# 15_LMS2_RF1_Misc.net
KiCad netlist of a schematic drawn in Altium Designer
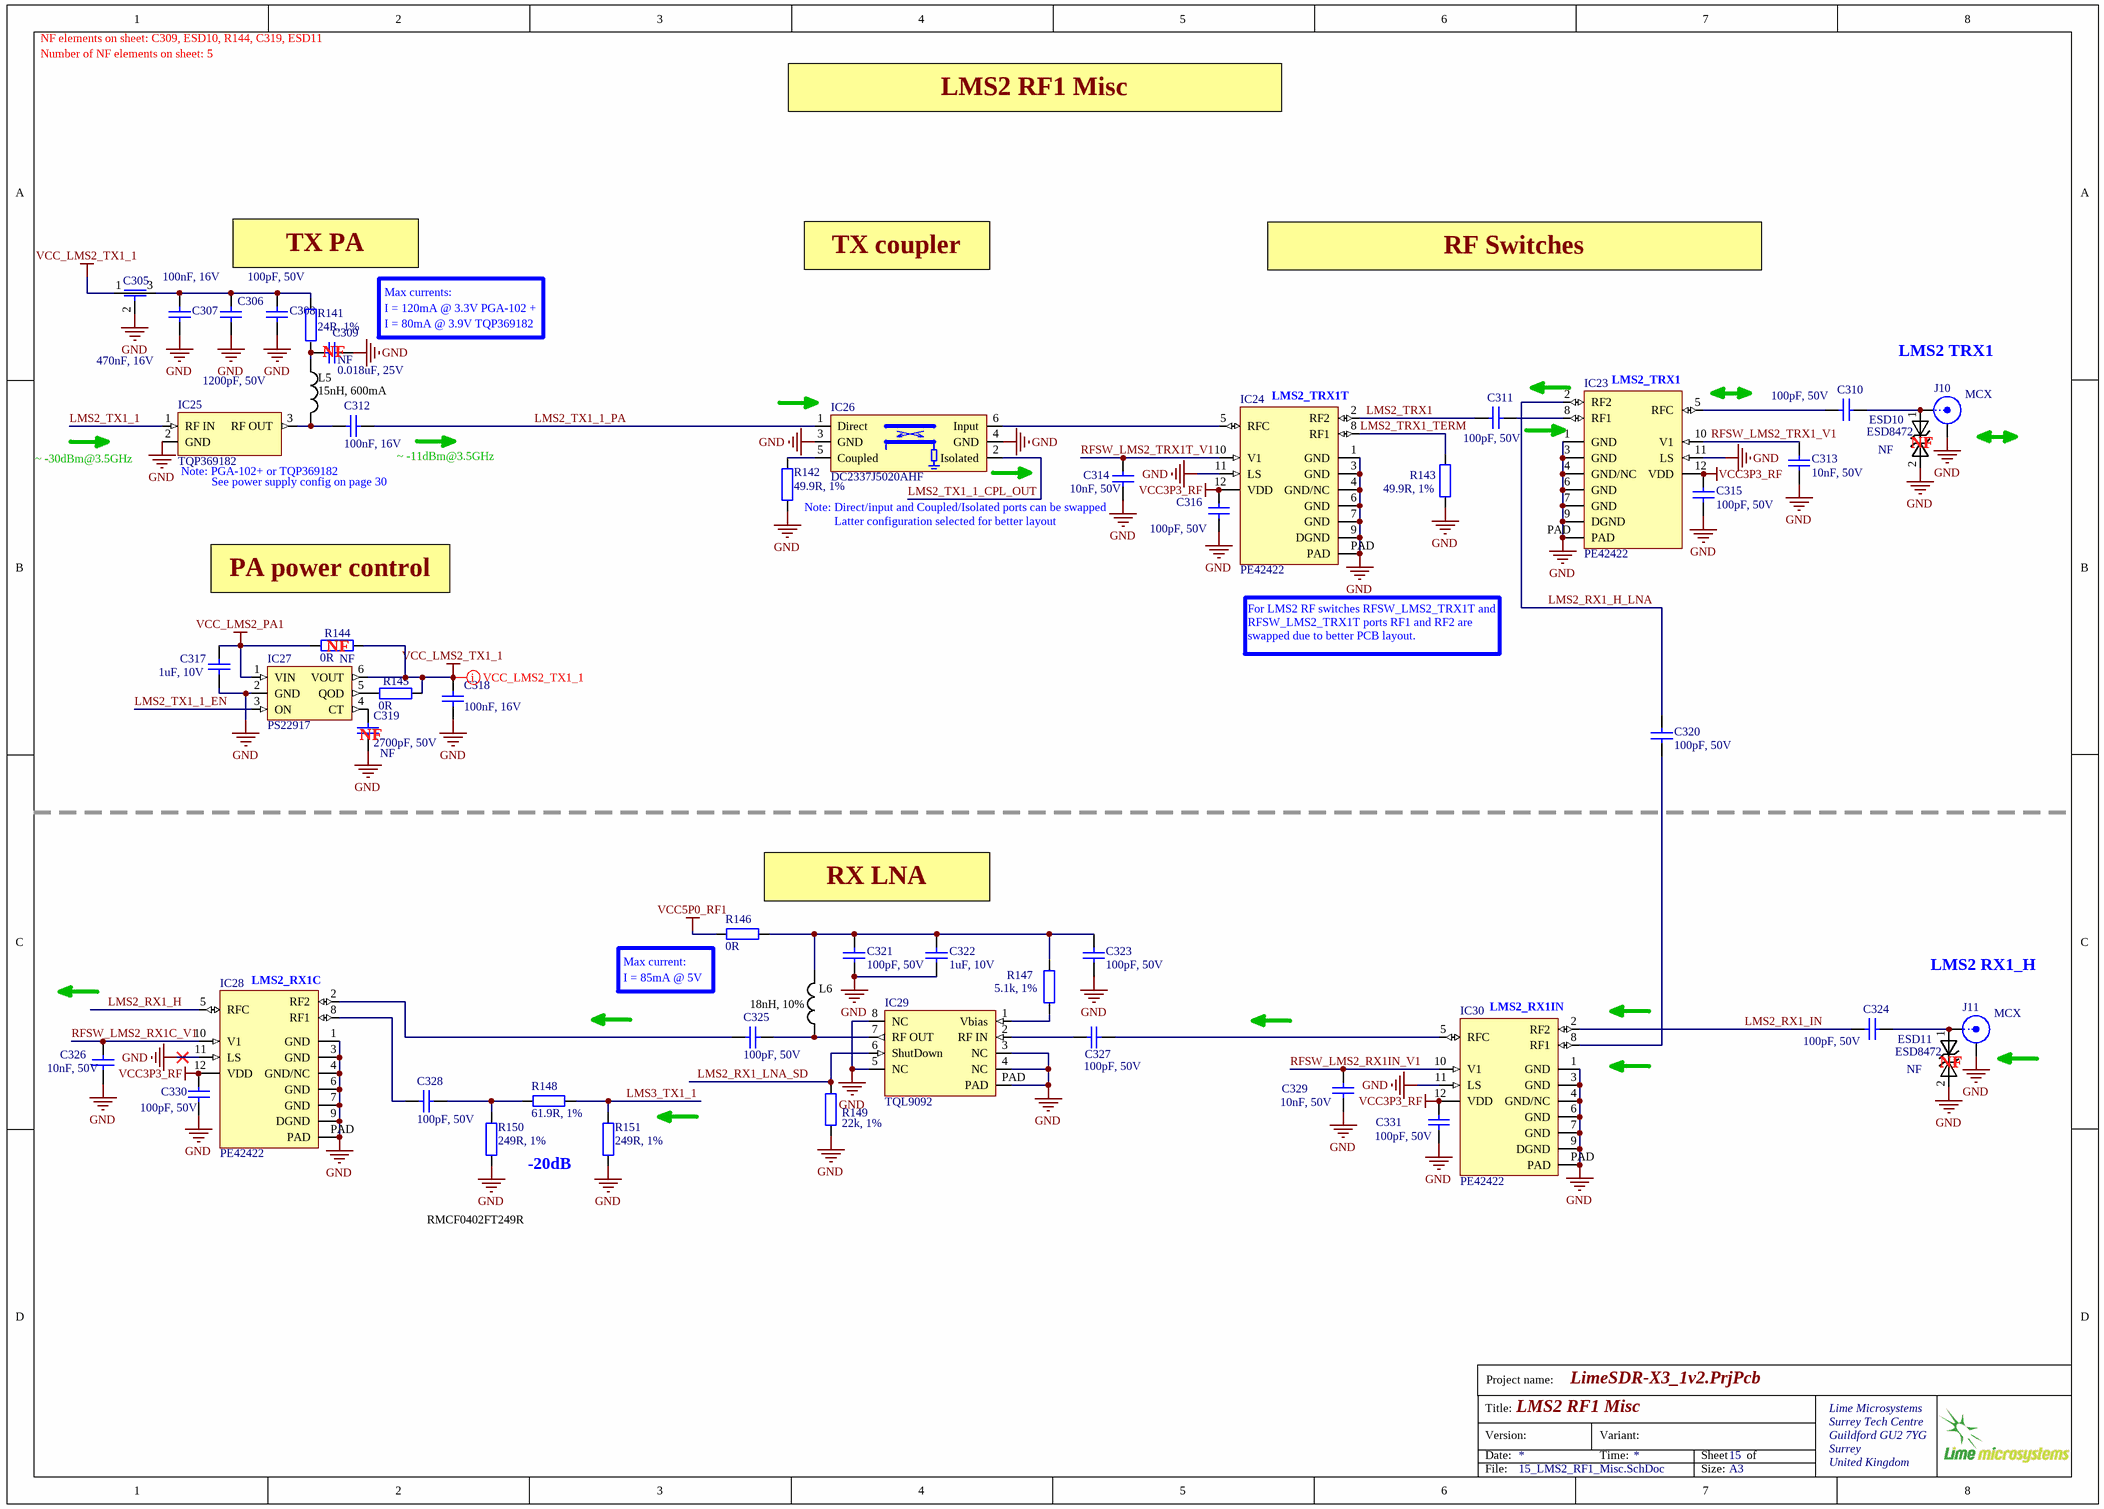
[diagram p0: 15_LMS2_RF1_Misc.SchDoc]

(export (version "E")
  (design (tool "Eeschema 10.0.6"))
  (components
    (comp (ref "C305")
      (value "470nF, 16V")
      (footprint "CAP0805_FEEDTHROUGH")
      (fields
        (field (name "MANUFACTURER") "Murata")
        (field (name "TOLERANCE") "20%")
        (field (name "VOLTAGE") "16V")
      )
      (libsource (lib "LimeMicroAltiumLib_schLib_r01") (part "Cap_feed_through"))
    )
    (comp (ref "C306")
      (value "1200pF, 50V")
      (footprint "CAP0402")
      (fields (field (name "MANUFACTURER") "Kemet") (field (name "TOLERANCE") "±5%"))
      (libsource (lib "") (part "Cap_0402_11"))
    )
    (comp (ref "C307")
      (value "100nF, 16V")
      (footprint "CAP0402")
      (fields (field (name "MANUFACTURER") "Murata Electronics") (field (name "TOLERANCE") "10 %"))
      (libsource (lib "") (part "Cap_0402_2"))
    )
    (comp (ref "C308")
      (value "100pF, 50V")
      (footprint "CAP0402")
      (fields (field (name "TOLERANCE") "±5%") (field (name "MANUFACTURER") "Yageo"))
      (libsource (lib "") (part "Cap_0402_2"))
    )
    (comp (ref "C309")
      (value "0.018uF, 25V")
      (footprint "CAP0402")
      (fields
        (field (name "ASSEMBLY INFO") "NF")
        (field (name "MANUFACTURER") "Yageo")
        (field (name "TOLERANCE") "10%")
      )
      (libsource (lib "") (part "Cap_0402_10"))
    )
    (comp (ref "C310")
      (value "100pF, 50V")
      (footprint "CAP0402")
      (fields (field (name "TOLERANCE") "±5%") (field (name "MANUFACTURER") "Yageo"))
      (libsource (lib "") (part "Cap_0402_1"))
    )
    (comp (ref "C311")
      (value "100pF, 50V")
      (footprint "CAP0402")
      (fields (field (name "TOLERANCE") "±5%") (field (name "MANUFACTURER") "Yageo"))
      (libsource (lib "") (part "Cap_0402_1"))
    )
    (comp (ref "C312")
      (value "100nF, 16V")
      (footprint "CAP0402")
      (fields (field (name "MANUFACTURER") "Murata Electronics") (field (name "TOLERANCE") "10 %"))
      (libsource (lib "") (part "Cap_0402_3"))
    )
    (comp (ref "C313")
      (value "10nF, 50V")
      (footprint "CAP0402")
      (fields
        (field (name "MANUFACTURER") "Murata Electronics North America")
        (field (name "TOLERANCE") "±10%")
      )
      (libsource (lib "") (part "Cap_0402_6"))
    )
    (comp (ref "C314")
      (value "10nF, 50V")
      (footprint "CAP0402")
      (fields
        (field (name "MANUFACTURER") "Murata Electronics North America")
        (field (name "TOLERANCE") "±10%")
      )
      (libsource (lib "") (part "Cap_0402_6"))
    )
    (comp (ref "C315")
      (value "100pF, 50V")
      (footprint "CAP0402")
      (fields (field (name "TOLERANCE") "±5%") (field (name "MANUFACTURER") "Yageo"))
      (libsource (lib "") (part "Cap_0402_9"))
    )
    (comp (ref "C316")
      (value "100pF, 50V")
      (footprint "CAP0402")
      (fields (field (name "TOLERANCE") "±5%") (field (name "MANUFACTURER") "Yageo"))
      (libsource (lib "") (part "Cap_0402_9"))
    )
    (comp (ref "C317")
      (value "1uF, 10V")
      (footprint "CAP0402")
      (fields (field (name "MANUFACTURER") "TDK"))
      (libsource (lib "LimeMicroAltiumLib_schLib") (part "Cap_0402"))
    )
    (comp (ref "C318")
      (value "100nF, 16V")
      (footprint "CAP0402")
      (fields (field (name "MANUFACTURER") "Murata Electronics") (field (name "TOLERANCE") "10 %"))
      (libsource (lib "LimeMicroAltiumLib_schLib") (part "Cap_0402"))
    )
    (comp (ref "C319")
      (value "2700pF, 50V")
      (footprint "CAP0402")
      (fields
        (field (name "ASSEMBLY INFO") "NF")
        (field (name "TOLERANCE") "±10%")
        (field (name "MANUFACTURER") "Murata Electronics North America")
      )
      (libsource (lib "") (part "Cap_0402_2"))
    )
    (comp (ref "C320")
      (value "100pF, 50V")
      (footprint "CAP0402")
      (fields (field (name "TOLERANCE") "±5%") (field (name "MANUFACTURER") "Yageo"))
      (libsource (lib "") (part "Cap_0402_1"))
    )
    (comp (ref "C321")
      (value "100pF, 50V")
      (footprint "CAP0402")
      (fields (field (name "TOLERANCE") "±5%") (field (name "MANUFACTURER") "Yageo"))
      (libsource (lib "") (part "Cap_0402_7"))
    )
    (comp (ref "C322")
      (value "1uF, 10V")
      (footprint "CAP0402")
      (fields (field (name "MANUFACTURER") "TDK"))
      (libsource (lib "") (part "Cap_0402_4"))
    )
    (comp (ref "C323")
      (value "100pF, 50V")
      (footprint "CAP0402")
      (fields (field (name "TOLERANCE") "±5%") (field (name "MANUFACTURER") "Yageo"))
      (libsource (lib "") (part "Cap_0402_7"))
    )
    (comp (ref "C324")
      (value "100pF, 50V")
      (footprint "CAP0402")
      (fields (field (name "TOLERANCE") "±5%") (field (name "MANUFACTURER") "Yageo"))
      (libsource (lib "") (part "Cap_0402_1"))
    )
    (comp (ref "C325")
      (value "100pF, 50V")
      (footprint "CAP0402")
      (fields (field (name "TOLERANCE") "±5%") (field (name "MANUFACTURER") "Yageo"))
      (libsource (lib "LimeMicroAltiumLib_schLib") (part "Cap_0402"))
    )
    (comp (ref "C326")
      (value "10nF, 50V")
      (footprint "CAP0402")
      (fields
        (field (name "MANUFACTURER") "Murata Electronics North America")
        (field (name "TOLERANCE") "±10%")
      )
      (libsource (lib "") (part "Cap_0402_5"))
    )
    (comp (ref "C327")
      (value "100pF, 50V")
      (footprint "CAP0402")
      (fields (field (name "TOLERANCE") "±5%") (field (name "MANUFACTURER") "Yageo"))
      (libsource (lib "LimeMicroAltiumLib_schLib") (part "Cap_0402"))
    )
    (comp (ref "C328")
      (value "100pF, 50V")
      (footprint "CAP0402")
      (fields (field (name "TOLERANCE") "±5%") (field (name "MANUFACTURER") "Yageo"))
      (libsource (lib "") (part "Cap_0402_1"))
    )
    (comp (ref "C329")
      (value "10nF, 50V")
      (footprint "CAP0402")
      (fields
        (field (name "MANUFACTURER") "Murata Electronics North America")
        (field (name "TOLERANCE") "±10%")
      )
      (libsource (lib "") (part "Cap_0402_10"))
    )
    (comp (ref "C330")
      (value "100pF, 50V")
      (footprint "CAP0402")
      (fields (field (name "TOLERANCE") "±5%") (field (name "MANUFACTURER") "Yageo"))
      (libsource (lib "") (part "Cap_0402_8"))
    )
    (comp (ref "C331")
      (value "100pF, 50V")
      (footprint "CAP0402")
      (fields (field (name "TOLERANCE") "±5%") (field (name "MANUFACTURER") "Yageo"))
      (libsource (lib "") (part "Cap_0402_3"))
    )
    (comp (ref "ESD10")
      (value "ESD8472")
      (footprint "ESD8472_X3DFN2")
      (fields (field (name "MANUFACTURER") "ON Semiconductor") (field (name "ASSEMBLY INFO") "NF"))
      (libsource (lib "LimeMicroAltiumLib_schLib") (part "ESD8472"))
    )
    (comp (ref "ESD11")
      (value "ESD8472")
      (footprint "ESD8472_X3DFN2")
      (fields (field (name "MANUFACTURER") "ON Semiconductor") (field (name "ASSEMBLY INFO") "NF"))
      (libsource (lib "") (part "ESD8472_1"))
    )
    (comp (ref "IC23")
      (value "PE42422")
      (footprint "PE42422_QFN12")
      (fields (field (name "MANUFACTURER") "Peregrine Semiconductor"))
      (libsource (lib "") (part "PE42422_2"))
    )
    (comp (ref "IC24")
      (value "PE42422")
      (footprint "PE42422_QFN12")
      (fields (field (name "MANUFACTURER") "Peregrine Semiconductor"))
      (libsource (lib "LimeMicroAltiumLib_schLib") (part "PE42422"))
    )
    (comp (ref "IC25")
      (value "TQP369182")
      (footprint "PGA-102+_SOT89")
      (fields (field (name "MANUFACTURER") "Qorvo"))
      (libsource (lib "LimeMicroAltiumLib_schLib_r01") (part "PGA-102+_PA"))
    )
    (comp (ref "IC26")
      (value "DC2337J5020AHF")
      (footprint "DC2337J5020AHF_ANAREN_COUPLER_0805")
      (fields (field (name "MANUFACTURER") "Anaren"))
      (libsource (lib "LimeMicroAltiumLib_schLib_r02") (part "DC2337J5020AHF_coupler"))
    )
    (comp (ref "IC27")
      (value "PS22917")
      (footprint "SOT23-6")
      (fields (field (name "MANUFACTURER") "Texas Instruments"))
      (libsource (lib "LimeMicroAltiumLib_schLib") (part "TPS22918"))
    )
    (comp (ref "IC28")
      (value "PE42422")
      (footprint "PE42422_QFN12")
      (fields (field (name "MANUFACTURER") "Peregrine Semiconductor"))
      (libsource (lib "") (part "PE42422_3"))
    )
    (comp (ref "IC29")
      (value "TQL9092")
      (footprint "TQL9092")
      (fields (field (name "MANUFACTURER") "Qorvo"))
      (libsource (lib "LimeMicroAltiumLib_schLib") (part "TQL9092"))
    )
    (comp (ref "IC30")
      (value "PE42422")
      (footprint "PE42422_QFN12")
      (fields (field (name "MANUFACTURER") "Peregrine Semiconductor"))
      (libsource (lib "") (part "PE42422_1"))
    )
    (comp (ref "J10")
      (value "MCX")
      (footprint "MCX_connector_vertical_SM")
      (fields (field (name "MANUFACTURER") "Bel Cinch"))
      (libsource (lib "LimeMicroAltiumLib_schLib") (part "RF_IF_connector"))
    )
    (comp (ref "J11")
      (value "MCX")
      (footprint "MCX_connector_vertical_SM")
      (fields (field (name "MANUFACTURER") "Bel Cinch"))
      (libsource (lib "LimeMicroAltiumLib_schLib") (part "RF_IF_connector"))
    )
    (comp (ref "L5")
      (value "15nH, 600mA")
      (footprint "RES0805")
      (fields (field (name "MANUFACTURER") "Bourns") (field (name "TOLERANCE") "5%"))
      (libsource (lib "LimeMicroAltiumLib_schLib") (part "Inductor_0603"))
    )
    (comp (ref "L6")
      (value "18nH, 10%")
      (footprint "RES0603")
      (fields (field (name "MANUFACTURER") "Pulse Electronics Network") (field (name "TOLERANCE") "±10%"))
      (libsource (lib "LimeMicroAltiumLib_schLib") (part "Inductor"))
    )
    (comp (ref "R141")
      (value "24R, 1%")
      (footprint "RES0402")
      (fields (field (name "MANUFACTURER") "Yageo") (field (name "TOLERANCE") "1%"))
      (libsource (lib "LimeFPGAboard_schLib") (part "Res_0402"))
    )
    (comp (ref "R142")
      (value "49.9R, 1%")
      (footprint "RES0402")
      (fields
        (field (name "TOLERANCE") "±1%")
        (field (name "MANUFACTURER") "Samsung Electro-Mechanics America, Inc.")
        (field (name "MANUFACTURER PART NUMBER") "RC1005F49R9CS")
      )
      (libsource (lib "") (part "Res_0402_1"))
    )
    (comp (ref "R143")
      (value "49.9R, 1%")
      (footprint "RES0402")
      (fields
        (field (name "TOLERANCE") "±1%")
        (field (name "MANUFACTURER") "Samsung Electro-Mechanics America, Inc.")
        (field (name "MANUFACTURER PART NUMBER") "RC1005F49R9CS")
      )
      (libsource (lib "") (part "Res_0402_1"))
    )
    (comp (ref "R144")
      (value "0R")
      (footprint "RES0402")
      (fields
        (field (name "ASSEMBLY INFO") "NF")
        (field (name "MANUFACTURER") "Yageo")
        (field (name "TOLERANCE") "Jumper")
      )
      (libsource (lib "LimeMicroAltiumLib_schLib") (part "Res_0402"))
    )
    (comp (ref "R145")
      (value "0R")
      (footprint "RES0402")
      (fields (field (name "MANUFACTURER") "Yageo") (field (name "TOLERANCE") "Jumper"))
      (libsource (lib "LimeMicroAltiumLib_schLib") (part "Res_0402"))
    )
    (comp (ref "R146")
      (value "0R")
      (footprint "RES0402")
      (fields (field (name "MANUFACTURER") "Yageo") (field (name "TOLERANCE") "Jumper"))
      (libsource (lib "") (part "Res_0402_1"))
    )
    (comp (ref "R147")
      (value "5.1k, 1%")
      (footprint "RES0603")
      (fields (field (name "MANUFACTURER") "Stackpole Electronics") (field (name "TOLERANCE") "1%"))
      (libsource (lib "LimeMicroAltiumLib_schLib") (part "Res_0603"))
    )
    (comp (ref "R148")
      (value "61.9R, 1%")
      (footprint "RES0402")
      (fields (field (name "MANUFACTURER") "Yageo") (field (name "TOLERANCE") "1%"))
      (libsource (lib "LimeMicroAltiumLib_schLib") (part "Res_0402"))
    )
    (comp (ref "R149")
      (value "22k, 1%")
      (footprint "RES0402")
      (fields (field (name "MANUFACTURER") "Yageo") (field (name "TOLERANCE") "±1%"))
      (libsource (lib "LimeMicroAltiumLib_schLib") (part "Res_0402"))
    )
    (comp (ref "R150")
      (value "249R, 1%")
      (footprint "RES0402")
      (fields (field (name "MANUFACTURER") "Stackpole Electronics Inc") (field (name "TOLERANCE") "±1%"))
      (libsource (lib "LimeMicroAltiumLib_schLib") (part "Res_0402"))
    )
    (comp (ref "R151")
      (value "249R, 1%")
      (footprint "RES0402")
      (fields (field (name "MANUFACTURER") "Stackpole Electronics Inc") (field (name "TOLERANCE") "±1%"))
      (libsource (lib "LimeMicroAltiumLib_schLib") (part "Res_0402"))
    )
  )
  (nets
    (net (code "1") (name "/LMS2_RX1_H") (class "Default")
      (node (ref "IC28") (pin "5") (pinfunction "RFC_5") (pintype "bidirectional"))
    )
    (net (code "2") (name "/LMS2_RX1_H_LNA") (class "Default")
      (node (ref "C320") (pin "2") (pinfunction "2_2") (pintype "passive"))
      (node (ref "IC23") (pin "2") (pinfunction "RF2_2") (pintype "bidirectional"))
    )
    (net (code "3") (name "/LMS2_RX1_IN") (class "Default")
      (node (ref "C324") (pin "1") (pinfunction "1_1") (pintype "passive"))
      (node (ref "IC30") (pin "2") (pinfunction "RF2_2") (pintype "bidirectional"))
    )
    (net (code "4") (name "/LMS2_RX1_LNA_SD") (class "Default")
      (node (ref "IC29") (pin "6") (pinfunction "ShutDown_6") (pintype "input"))
      (node (ref "R149") (pin "2") (pinfunction "2_2") (pintype "passive"))
    )
    (net (code "5") (name "/LMS2_TRX1") (class "Default")
      (node (ref "C311") (pin "1") (pinfunction "1_1") (pintype "passive"))
      (node (ref "IC24") (pin "2") (pinfunction "RF2_2") (pintype "bidirectional"))
    )
    (net (code "6") (name "/LMS2_TRX1_TERM") (class "Default")
      (node (ref "IC24") (pin "8") (pinfunction "RF1_8") (pintype "bidirectional"))
      (node (ref "R143") (pin "1") (pinfunction "1_1") (pintype "passive"))
    )
    (net (code "7") (name "/LMS2_TX1_1") (class "Default")
      (node (ref "IC25") (pin "1") (pinfunction "RF_IN_1") (pintype "input"))
    )
    (net (code "8") (name "/LMS2_TX1_1_CPL_OUT") (class "Default")
      (node (ref "IC26") (pin "2") (pinfunction "Isolated_2") (pintype "passive"))
    )
    (net (code "9") (name "/LMS2_TX1_1_EN") (class "Default")
      (node (ref "IC27") (pin "3") (pinfunction "ON_3") (pintype "input"))
    )
    (net (code "10") (name "/LMS2_TX1_1_PA") (class "Default")
      (node (ref "C312") (pin "1") (pinfunction "1_1") (pintype "passive"))
      (node (ref "IC26") (pin "1") (pinfunction "Direct_1") (pintype "passive"))
    )
    (net (code "11") (name "/LMS3_TX1_1") (class "Default")
      (node (ref "R148") (pin "2") (pinfunction "2_2") (pintype "passive"))
      (node (ref "R151") (pin "2") (pinfunction "2_2") (pintype "passive"))
    )
    (net (code "12") (name "/RFSW_LMS2_RX1C_V1") (class "Default")
      (node (ref "C326") (pin "1") (pinfunction "1_1") (pintype "passive"))
      (node (ref "IC28") (pin "10") (pinfunction "V1_10") (pintype "input"))
    )
    (net (code "13") (name "/RFSW_LMS2_RX1IN_V1") (class "Default")
      (node (ref "C329") (pin "1") (pinfunction "1_1") (pintype "passive"))
      (node (ref "IC30") (pin "10") (pinfunction "V1_10") (pintype "input"))
    )
    (net (code "14") (name "/RFSW_LMS2_TRX1T_V1") (class "Default")
      (node (ref "C314") (pin "1") (pinfunction "1_1") (pintype "passive"))
      (node (ref "IC24") (pin "10") (pinfunction "V1_10") (pintype "input"))
    )
    (net (code "15") (name "/RFSW_LMS2_TRX1_V1") (class "Default")
      (node (ref "C313") (pin "1") (pinfunction "1_1") (pintype "passive"))
      (node (ref "IC23") (pin "10") (pinfunction "V1_10") (pintype "input"))
    )
    (net (code "16") (name "GND") (class "Default")
      (node (ref "C305") (pin "2") (pinfunction "2_2") (pintype "passive"))
      (node (ref "C306") (pin "2") (pinfunction "2_2") (pintype "passive"))
      (node (ref "C307") (pin "1") (pinfunction "1_1") (pintype "passive"))
      (node (ref "C308") (pin "2") (pinfunction "2_2") (pintype "passive"))
      (node (ref "C309") (pin "2") (pinfunction "2_2") (pintype "passive"))
      (node (ref "C313") (pin "2") (pinfunction "2_2") (pintype "passive"))
      (node (ref "C314") (pin "2") (pinfunction "2_2") (pintype "passive"))
      (node (ref "C315") (pin "1") (pinfunction "1_1") (pintype "passive"))
      (node (ref "C316") (pin "1") (pinfunction "1_1") (pintype "passive"))
      (node (ref "C317") (pin "1") (pinfunction "1_1") (pintype "passive"))
      (node (ref "C318") (pin "1") (pinfunction "1_1") (pintype "passive"))
      (node (ref "C319") (pin "2") (pinfunction "2_2") (pintype "passive"))
      (node (ref "C321") (pin "2") (pinfunction "2_2") (pintype "passive"))
      (node (ref "C322") (pin "1") (pinfunction "1_1") (pintype "passive"))
      (node (ref "C323") (pin "2") (pinfunction "2_2") (pintype "passive"))
      (node (ref "C326") (pin "2") (pinfunction "2_2") (pintype "passive"))
      (node (ref "C329") (pin "2") (pinfunction "2_2") (pintype "passive"))
      (node (ref "C330") (pin "1") (pinfunction "1_1") (pintype "passive"))
      (node (ref "C331") (pin "1") (pinfunction "1_1") (pintype "passive"))
      (node (ref "ESD10") (pin "2") (pinfunction "2_2") (pintype "passive"))
      (node (ref "ESD11") (pin "2") (pinfunction "2_2") (pintype "passive"))
      (node (ref "IC23") (pin "1") (pinfunction "GND_1") (pintype "passive"))
      (node (ref "IC23") (pin "11") (pinfunction "LS_11") (pintype "input"))
      (node (ref "IC23") (pin "3") (pinfunction "GND_3") (pintype "passive"))
      (node (ref "IC23") (pin "4") (pinfunction "GND/NC_4") (pintype "passive"))
      (node (ref "IC23") (pin "6") (pinfunction "GND_6") (pintype "passive"))
      (node (ref "IC23") (pin "7") (pinfunction "GND_7") (pintype "passive"))
      (node (ref "IC23") (pin "9") (pinfunction "DGND_9") (pintype "passive"))
      (node (ref "IC23") (pin "PAD") (pinfunction "PAD_PAD") (pintype "passive"))
      (node (ref "IC24") (pin "1") (pinfunction "GND_1") (pintype "passive"))
      (node (ref "IC24") (pin "11") (pinfunction "LS_11") (pintype "input"))
      (node (ref "IC24") (pin "3") (pinfunction "GND_3") (pintype "passive"))
      (node (ref "IC24") (pin "4") (pinfunction "GND/NC_4") (pintype "passive"))
      (node (ref "IC24") (pin "6") (pinfunction "GND_6") (pintype "passive"))
      (node (ref "IC24") (pin "7") (pinfunction "GND_7") (pintype "passive"))
      (node (ref "IC24") (pin "9") (pinfunction "DGND_9") (pintype "passive"))
      (node (ref "IC24") (pin "PAD") (pinfunction "PAD_PAD") (pintype "passive"))
      (node (ref "IC25") (pin "2") (pinfunction "GND_2") (pintype "passive"))
      (node (ref "IC26") (pin "3") (pinfunction "GND_3") (pintype "passive"))
      (node (ref "IC26") (pin "4") (pinfunction "GND_4") (pintype "passive"))
      (node (ref "IC27") (pin "2") (pinfunction "GND_2") (pintype "passive"))
      (node (ref "IC28") (pin "1") (pinfunction "GND_1") (pintype "passive"))
      (node (ref "IC28") (pin "11") (pinfunction "LS_11") (pintype "input"))
      (node (ref "IC28") (pin "3") (pinfunction "GND_3") (pintype "passive"))
      (node (ref "IC28") (pin "4") (pinfunction "GND/NC_4") (pintype "passive"))
      (node (ref "IC28") (pin "6") (pinfunction "GND_6") (pintype "passive"))
      (node (ref "IC28") (pin "7") (pinfunction "GND_7") (pintype "passive"))
      (node (ref "IC28") (pin "9") (pinfunction "DGND_9") (pintype "passive"))
      (node (ref "IC28") (pin "PAD") (pinfunction "PAD_PAD") (pintype "passive"))
      (node (ref "IC29") (pin "3") (pinfunction "NC_3") (pintype "passive"))
      (node (ref "IC29") (pin "4") (pinfunction "NC_4") (pintype "passive"))
      (node (ref "IC29") (pin "5") (pinfunction "NC_5") (pintype "passive"))
      (node (ref "IC29") (pin "8") (pinfunction "NC_8") (pintype "passive"))
      (node (ref "IC29") (pin "PAD") (pinfunction "PAD_PAD") (pintype "passive"))
      (node (ref "IC30") (pin "1") (pinfunction "GND_1") (pintype "passive"))
      (node (ref "IC30") (pin "11") (pinfunction "LS_11") (pintype "input"))
      (node (ref "IC30") (pin "3") (pinfunction "GND_3") (pintype "passive"))
      (node (ref "IC30") (pin "4") (pinfunction "GND/NC_4") (pintype "passive"))
      (node (ref "IC30") (pin "6") (pinfunction "GND_6") (pintype "passive"))
      (node (ref "IC30") (pin "7") (pinfunction "GND_7") (pintype "passive"))
      (node (ref "IC30") (pin "9") (pinfunction "DGND_9") (pintype "passive"))
      (node (ref "IC30") (pin "PAD") (pinfunction "PAD_PAD") (pintype "passive"))
      (node (ref "J10") (pin "2") (pinfunction "Y_2") (pintype "passive"))
      (node (ref "J11") (pin "2") (pinfunction "Y_2") (pintype "passive"))
      (node (ref "R142") (pin "2") (pinfunction "2_2") (pintype "passive"))
      (node (ref "R143") (pin "2") (pinfunction "2_2") (pintype "passive"))
      (node (ref "R149") (pin "1") (pinfunction "1_1") (pintype "passive"))
      (node (ref "R150") (pin "1") (pinfunction "1_1") (pintype "passive"))
      (node (ref "R151") (pin "1") (pinfunction "1_1") (pintype "passive"))
    )
    (net (code "17") (name "Net-(C305-Pad3)") (class "Default")
      (node (ref "C305") (pin "3") (pinfunction "3_3") (pintype "passive"))
      (node (ref "C306") (pin "1") (pinfunction "1_1") (pintype "passive"))
      (node (ref "C307") (pin "2") (pinfunction "2_2") (pintype "passive"))
      (node (ref "C308") (pin "1") (pinfunction "1_1") (pintype "passive"))
      (node (ref "R141") (pin "1") (pinfunction "1_1") (pintype "passive"))
    )
    (net (code "18") (name "Net-(C309-Pad1)") (class "Default")
      (node (ref "C309") (pin "1") (pinfunction "1_1") (pintype "passive"))
      (node (ref "L5") (pin "1") (pinfunction "1_1") (pintype "passive"))
      (node (ref "R141") (pin "2") (pinfunction "2_2") (pintype "passive"))
    )
    (net (code "19") (name "Net-(C321-Pad1)") (class "Default")
      (node (ref "C321") (pin "1") (pinfunction "1_1") (pintype "passive"))
      (node (ref "C322") (pin "2") (pinfunction "2_2") (pintype "passive"))
      (node (ref "C323") (pin "1") (pinfunction "1_1") (pintype "passive"))
      (node (ref "L6") (pin "1") (pinfunction "1_1") (pintype "passive"))
      (node (ref "R146") (pin "2") (pinfunction "2_2") (pintype "passive"))
      (node (ref "R147") (pin "2") (pinfunction "2_2") (pintype "passive"))
    )
    (net (code "20") (name "Net-(C328-Pad1)") (class "Default")
      (node (ref "C328") (pin "1") (pinfunction "1_1") (pintype "passive"))
      (node (ref "R148") (pin "1") (pinfunction "1_1") (pintype "passive"))
      (node (ref "R150") (pin "2") (pinfunction "2_2") (pintype "passive"))
    )
    (net (code "21") (name "Net-(IC23-RF1)") (class "Default")
      (node (ref "C311") (pin "2") (pinfunction "2_2") (pintype "passive"))
      (node (ref "IC23") (pin "8") (pinfunction "RF1_8") (pintype "bidirectional"))
    )
    (net (code "22") (name "Net-(IC23-RFC)") (class "Default")
      (node (ref "C310") (pin "1") (pinfunction "1_1") (pintype "passive"))
      (node (ref "IC23") (pin "5") (pinfunction "RFC_5") (pintype "bidirectional"))
    )
    (net (code "23") (name "Net-(IC24-RFC)") (class "Default")
      (node (ref "IC24") (pin "5") (pinfunction "RFC_5") (pintype "bidirectional"))
      (node (ref "IC26") (pin "6") (pinfunction "Input_6") (pintype "passive"))
    )
    (net (code "24") (name "Net-(IC25-RF_OUT)") (class "Default")
      (node (ref "C312") (pin "2") (pinfunction "2_2") (pintype "passive"))
      (node (ref "IC25") (pin "3") (pinfunction "RF_OUT_3") (pintype "output"))
      (node (ref "L5") (pin "2") (pinfunction "2_2") (pintype "passive"))
    )
    (net (code "25") (name "Net-(IC26-Coupled)") (class "Default")
      (node (ref "IC26") (pin "5") (pinfunction "Coupled_5") (pintype "passive"))
      (node (ref "R142") (pin "1") (pinfunction "1_1") (pintype "passive"))
    )
    (net (code "26") (name "Net-(IC27-CT)") (class "Default")
      (node (ref "C319") (pin "1") (pinfunction "1_1") (pintype "passive"))
      (node (ref "IC27") (pin "4") (pinfunction "CT_4") (pintype "output"))
    )
    (net (code "27") (name "Net-(IC27-QOD)") (class "Default")
      (node (ref "IC27") (pin "5") (pinfunction "QOD_5") (pintype "output"))
      (node (ref "R145") (pin "2") (pinfunction "2_2") (pintype "passive"))
    )
    (net (code "28") (name "Net-(IC28-RF1)") (class "Default")
      (node (ref "C328") (pin "2") (pinfunction "2_2") (pintype "passive"))
      (node (ref "IC28") (pin "8") (pinfunction "RF1_8") (pintype "bidirectional"))
    )
    (net (code "29") (name "Net-(IC28-RF2)") (class "Default")
      (node (ref "C325") (pin "1") (pinfunction "1_1") (pintype "passive"))
      (node (ref "IC28") (pin "2") (pinfunction "RF2_2") (pintype "bidirectional"))
    )
    (net (code "30") (name "Net-(IC29-RF_IN)") (class "Default")
      (node (ref "C327") (pin "1") (pinfunction "1_1") (pintype "passive"))
      (node (ref "IC29") (pin "2") (pinfunction "RF_IN_2") (pintype "input"))
    )
    (net (code "31") (name "Net-(IC29-RF_OUT)") (class "Default")
      (node (ref "C325") (pin "2") (pinfunction "2_2") (pintype "passive"))
      (node (ref "IC29") (pin "7") (pinfunction "RF_OUT_7") (pintype "output"))
      (node (ref "L6") (pin "2") (pinfunction "2_2") (pintype "passive"))
    )
    (net (code "32") (name "Net-(IC29-Vbias)") (class "Default")
      (node (ref "IC29") (pin "1") (pinfunction "Vbias_1") (pintype "input"))
      (node (ref "R147") (pin "1") (pinfunction "1_1") (pintype "passive"))
    )
    (net (code "33") (name "Net-(IC30-RF1)") (class "Default")
      (node (ref "C320") (pin "1") (pinfunction "1_1") (pintype "passive"))
      (node (ref "IC30") (pin "8") (pinfunction "RF1_8") (pintype "bidirectional"))
    )
    (net (code "34") (name "Net-(IC30-RFC)") (class "Default")
      (node (ref "C327") (pin "2") (pinfunction "2_2") (pintype "passive"))
      (node (ref "IC30") (pin "5") (pinfunction "RFC_5") (pintype "bidirectional"))
    )
    (net (code "35") (name "Net-(J10-X)") (class "Default")
      (node (ref "C310") (pin "2") (pinfunction "2_2") (pintype "passive"))
      (node (ref "ESD10") (pin "1") (pinfunction "1_1") (pintype "passive"))
      (node (ref "J10") (pin "1") (pinfunction "X_1") (pintype "passive"))
    )
    (net (code "36") (name "Net-(J11-X)") (class "Default")
      (node (ref "C324") (pin "2") (pinfunction "2_2") (pintype "passive"))
      (node (ref "ESD11") (pin "1") (pinfunction "1_1") (pintype "passive"))
      (node (ref "J11") (pin "1") (pinfunction "X_1") (pintype "passive"))
    )
    (net (code "37") (name "VCC3P3_RF") (class "Default")
      (node (ref "C315") (pin "2") (pinfunction "2_2") (pintype "passive"))
      (node (ref "C316") (pin "2") (pinfunction "2_2") (pintype "passive"))
      (node (ref "C330") (pin "2") (pinfunction "2_2") (pintype "passive"))
      (node (ref "C331") (pin "2") (pinfunction "2_2") (pintype "passive"))
      (node (ref "IC23") (pin "12") (pinfunction "VDD_12") (pintype "power_in"))
      (node (ref "IC24") (pin "12") (pinfunction "VDD_12") (pintype "power_in"))
      (node (ref "IC28") (pin "12") (pinfunction "VDD_12") (pintype "power_in"))
      (node (ref "IC30") (pin "12") (pinfunction "VDD_12") (pintype "power_in"))
    )
    (net (code "38") (name "VCC5P0_RF1") (class "Default")
      (node (ref "R146") (pin "1") (pinfunction "1_1") (pintype "passive"))
    )
    (net (code "39") (name "VCC_LMS2_PA1") (class "Default")
      (node (ref "C317") (pin "2") (pinfunction "2_2") (pintype "passive"))
      (node (ref "IC27") (pin "1") (pinfunction "VIN_1") (pintype "input"))
      (node (ref "R144") (pin "2") (pinfunction "2_2") (pintype "passive"))
    )
    (net (code "40") (name "VCC_LMS2_TX1_1") (class "Default")
      (node (ref "C305") (pin "1") (pinfunction "1_1") (pintype "passive"))
      (node (ref "C318") (pin "2") (pinfunction "2_2") (pintype "passive"))
      (node (ref "IC27") (pin "6") (pinfunction "VOUT_6") (pintype "output"))
      (node (ref "R144") (pin "1") (pinfunction "1_1") (pintype "passive"))
      (node (ref "R145") (pin "1") (pinfunction "1_1") (pintype "passive"))
    )
  )
)
